# Sheet2.net
KiCad netlist of a schematic drawn in Altium Designer
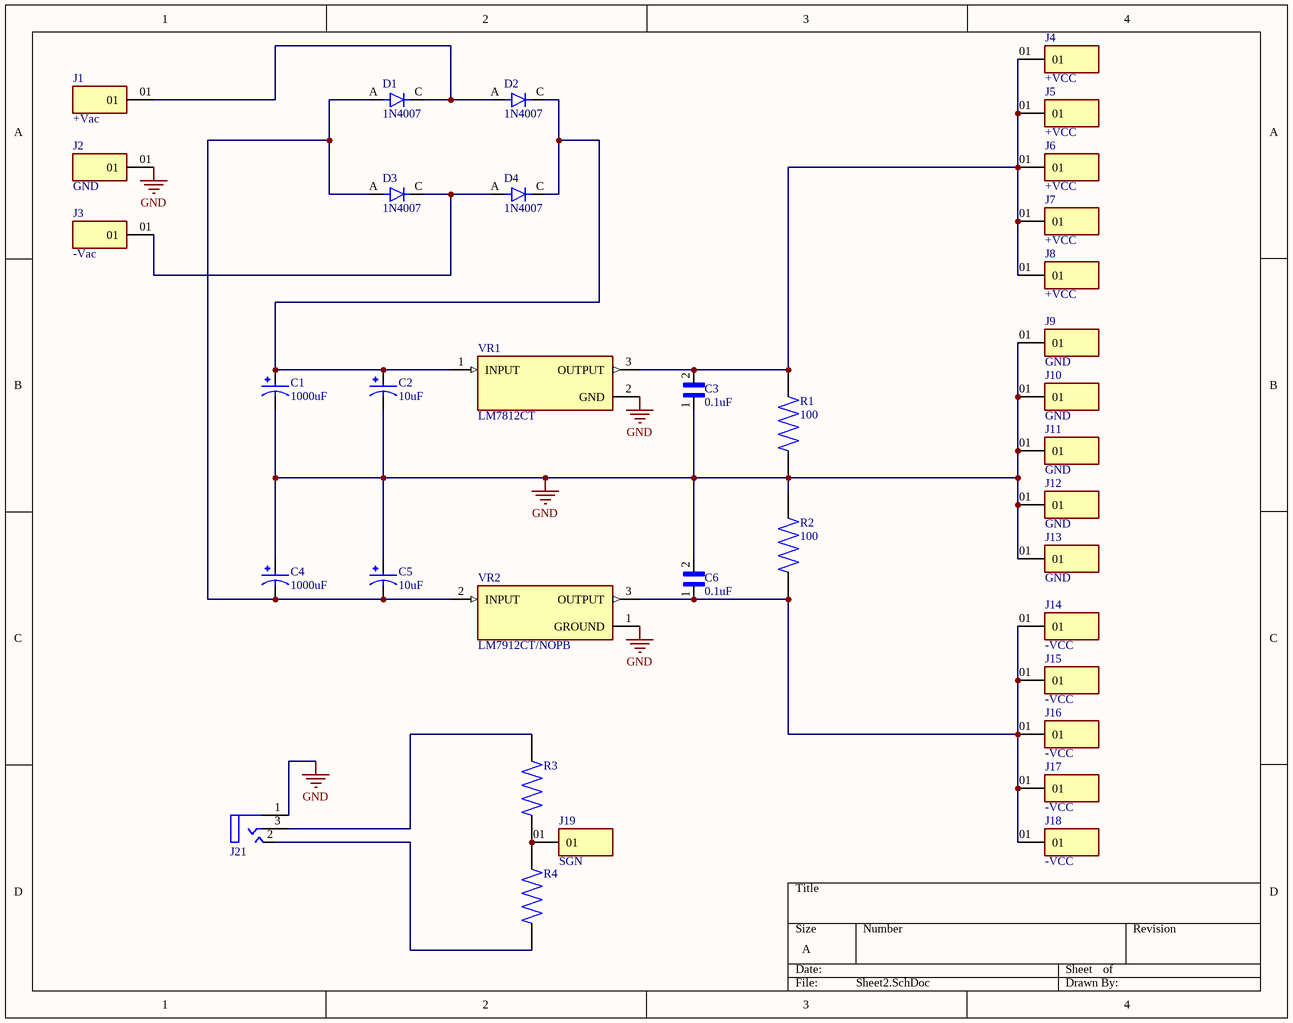
[diagram p0: Sheet2.SchDoc]

(export (version "E")
  (design (tool "Eeschema 10.0.6"))
  (components
    (comp (ref "C1")
      (value "1000uF")
      (footprint "CAPPRD750W80D1800H2500")
      (description "CAP ALUM 82UF 20% 350V RADIAL")
      (fields (field (name "MP") "EEU-EE2V820S") (field (name "MF") "Panasonic Electronic"))
      (libsource (lib "EEUEE2V820S") (part "EEUEE2V820S"))
    )
    (comp (ref "C2")
      (value "10uF")
      (footprint "CAPPRD750W80D1800H2500")
      (description "CAP ALUM 82UF 20% 350V RADIAL")
      (fields (field (name "MP") "EEU-EE2V820S") (field (name "MF") "Panasonic Electronic"))
      (libsource (lib "EEUEE2V820S") (part "EEUEE2V820S"))
    )
    (comp (ref "C3")
      (value "0.1uF")
      (footprint "CAPRB500W50L550T350H600:CAPRB500W50L550T350H600")
      (description "0.1ÂµF Â±10% 250V Ceramic Capacitor X7R Radial")
      (fields (field (name "MF") "TDK") (field (name "MP") "FG26X7R2E104KNT06"))
      (libsource (lib "FG26X7R2E104KNT06") (part "FG26X7R2E104KNT06"))
    )
    (comp (ref "C4")
      (value "1000uF")
      (footprint "CAPPRD750W80D1800H2500")
      (description "CAP ALUM 82UF 20% 350V RADIAL")
      (fields (field (name "MP") "EEU-EE2V820S") (field (name "MF") "Panasonic Electronic"))
      (libsource (lib "EEUEE2V820S") (part "EEUEE2V820S"))
    )
    (comp (ref "C5")
      (value "10uF")
      (footprint "CAPPRD750W80D1800H2500")
      (description "CAP ALUM 82UF 20% 350V RADIAL")
      (fields (field (name "MP") "EEU-EE2V820S") (field (name "MF") "Panasonic Electronic"))
      (libsource (lib "EEUEE2V820S") (part "EEUEE2V820S"))
    )
    (comp (ref "C6")
      (value "0.1uF")
      (footprint "CAPRB500W50L550T350H600:CAPRB500W50L550T350H600")
      (description "0.1ÂµF Â±10% 250V Ceramic Capacitor X7R Radial")
      (fields (field (name "MF") "TDK") (field (name "MP") "FG26X7R2E104KNT06"))
      (libsource (lib "FG26X7R2E104KNT06") (part "FG26X7R2E104KNT06"))
    )
    (comp (ref "D1")
      (value "1N4007")
      (footprint "DIOAD1060W80L520D270")
      (description "Diode Switching 1KV 1A 2-Pin DO-41")
      (libsource (lib "1N4007") (part "1N4007"))
    )
    (comp (ref "D2")
      (value "1N4007")
      (footprint "DIOAD1060W80L520D270")
      (description "Diode Switching 1KV 1A 2-Pin DO-41")
      (libsource (lib "1N4007") (part "1N4007"))
    )
    (comp (ref "D3")
      (value "1N4007")
      (footprint "DIOAD1060W80L520D270")
      (description "Diode Switching 1KV 1A 2-Pin DO-41")
      (libsource (lib "1N4007") (part "1N4007"))
    )
    (comp (ref "D4")
      (value "1N4007")
      (footprint "DIOAD1060W80L520D270")
      (description "Diode Switching 1KV 1A 2-Pin DO-41")
      (libsource (lib "1N4007") (part "1N4007"))
    )
    (comp (ref "J1")
      (value "+Vac")
      (footprint "SAMTEC_MTMM-101-XX-X-S-XXX:SAMTEC_MTMM-101-XX-X-S-XXX")
      (description "Connector Header position")
      (fields (field (name "MP") "MTMM-101-XX-X-S-XXX"))
      (libsource (lib "") (part "MTMM-101-XX-X-S-XXX_1"))
    )
    (comp (ref "J2")
      (value "GND")
      (footprint "SAMTEC_MTMM-101-XX-X-S-XXX:SAMTEC_MTMM-101-XX-X-S-XXX")
      (description "Connector Header position")
      (fields (field (name "MP") "MTMM-101-XX-X-S-XXX"))
      (libsource (lib "") (part "MTMM-101-XX-X-S-XXX_1"))
    )
    (comp (ref "J3")
      (value "-Vac")
      (footprint "SAMTEC_MTMM-101-XX-X-S-XXX:SAMTEC_MTMM-101-XX-X-S-XXX")
      (description "Connector Header position")
      (fields (field (name "MP") "MTMM-101-XX-X-S-XXX"))
      (libsource (lib "") (part "MTMM-101-XX-X-S-XXX_1"))
    )
    (comp (ref "J4")
      (value "+VCC")
      (footprint "SAMTEC_MTMM-101-XX-X-S-XXX:SAMTEC_MTMM-101-XX-X-S-XXX")
      (description "Connector Header position")
      (fields (field (name "MP") "MTMM-101-XX-X-S-XXX"))
      (libsource (lib "MTMM-101-XX-X-S-XXX") (part "MTMM-101-XX-X-S-XXX"))
    )
    (comp (ref "J5")
      (value "+VCC")
      (footprint "SAMTEC_MTMM-101-XX-X-S-XXX:SAMTEC_MTMM-101-XX-X-S-XXX")
      (description "Connector Header position")
      (fields (field (name "MP") "MTMM-101-XX-X-S-XXX"))
      (libsource (lib "MTMM-101-XX-X-S-XXX") (part "MTMM-101-XX-X-S-XXX"))
    )
    (comp (ref "J6")
      (value "+VCC")
      (footprint "SAMTEC_MTMM-101-XX-X-S-XXX:SAMTEC_MTMM-101-XX-X-S-XXX")
      (description "Connector Header position")
      (fields (field (name "MP") "MTMM-101-XX-X-S-XXX"))
      (libsource (lib "MTMM-101-XX-X-S-XXX") (part "MTMM-101-XX-X-S-XXX"))
    )
    (comp (ref "J7")
      (value "+VCC")
      (footprint "SAMTEC_MTMM-101-XX-X-S-XXX:SAMTEC_MTMM-101-XX-X-S-XXX")
      (description "Connector Header position")
      (fields (field (name "MP") "MTMM-101-XX-X-S-XXX"))
      (libsource (lib "MTMM-101-XX-X-S-XXX") (part "MTMM-101-XX-X-S-XXX"))
    )
    (comp (ref "J8")
      (value "+VCC")
      (footprint "SAMTEC_MTMM-101-XX-X-S-XXX:SAMTEC_MTMM-101-XX-X-S-XXX")
      (description "Connector Header position")
      (fields (field (name "MP") "MTMM-101-XX-X-S-XXX"))
      (libsource (lib "MTMM-101-XX-X-S-XXX") (part "MTMM-101-XX-X-S-XXX"))
    )
    (comp (ref "J9")
      (value "GND")
      (footprint "SAMTEC_MTMM-101-XX-X-S-XXX:SAMTEC_MTMM-101-XX-X-S-XXX")
      (description "Connector Header position")
      (fields (field (name "MP") "MTMM-101-XX-X-S-XXX"))
      (libsource (lib "MTMM-101-XX-X-S-XXX") (part "MTMM-101-XX-X-S-XXX"))
    )
    (comp (ref "J10")
      (value "GND")
      (footprint "SAMTEC_MTMM-101-XX-X-S-XXX:SAMTEC_MTMM-101-XX-X-S-XXX")
      (description "Connector Header position")
      (fields (field (name "MP") "MTMM-101-XX-X-S-XXX"))
      (libsource (lib "MTMM-101-XX-X-S-XXX") (part "MTMM-101-XX-X-S-XXX"))
    )
    (comp (ref "J11")
      (value "GND")
      (footprint "SAMTEC_MTMM-101-XX-X-S-XXX:SAMTEC_MTMM-101-XX-X-S-XXX")
      (description "Connector Header position")
      (fields (field (name "MP") "MTMM-101-XX-X-S-XXX"))
      (libsource (lib "MTMM-101-XX-X-S-XXX") (part "MTMM-101-XX-X-S-XXX"))
    )
    (comp (ref "J12")
      (value "GND")
      (footprint "SAMTEC_MTMM-101-XX-X-S-XXX:SAMTEC_MTMM-101-XX-X-S-XXX")
      (description "Connector Header position")
      (fields (field (name "MP") "MTMM-101-XX-X-S-XXX"))
      (libsource (lib "MTMM-101-XX-X-S-XXX") (part "MTMM-101-XX-X-S-XXX"))
    )
    (comp (ref "J13")
      (value "GND")
      (footprint "SAMTEC_MTMM-101-XX-X-S-XXX:SAMTEC_MTMM-101-XX-X-S-XXX")
      (description "Connector Header position")
      (fields (field (name "MP") "MTMM-101-XX-X-S-XXX"))
      (libsource (lib "MTMM-101-XX-X-S-XXX") (part "MTMM-101-XX-X-S-XXX"))
    )
    (comp (ref "J14")
      (value "-VCC")
      (footprint "SAMTEC_MTMM-101-XX-X-S-XXX:SAMTEC_MTMM-101-XX-X-S-XXX")
      (description "Connector Header position")
      (fields (field (name "MP") "MTMM-101-XX-X-S-XXX"))
      (libsource (lib "MTMM-101-XX-X-S-XXX") (part "MTMM-101-XX-X-S-XXX"))
    )
    (comp (ref "J15")
      (value "-VCC")
      (footprint "SAMTEC_MTMM-101-XX-X-S-XXX:SAMTEC_MTMM-101-XX-X-S-XXX")
      (description "Connector Header position")
      (fields (field (name "MP") "MTMM-101-XX-X-S-XXX"))
      (libsource (lib "MTMM-101-XX-X-S-XXX") (part "MTMM-101-XX-X-S-XXX"))
    )
    (comp (ref "J16")
      (value "-VCC")
      (footprint "SAMTEC_MTMM-101-XX-X-S-XXX:SAMTEC_MTMM-101-XX-X-S-XXX")
      (description "Connector Header position")
      (fields (field (name "MP") "MTMM-101-XX-X-S-XXX"))
      (libsource (lib "MTMM-101-XX-X-S-XXX") (part "MTMM-101-XX-X-S-XXX"))
    )
    (comp (ref "J17")
      (value "-VCC")
      (footprint "SAMTEC_MTMM-101-XX-X-S-XXX:SAMTEC_MTMM-101-XX-X-S-XXX")
      (description "Connector Header position")
      (fields (field (name "MP") "MTMM-101-XX-X-S-XXX"))
      (libsource (lib "MTMM-101-XX-X-S-XXX") (part "MTMM-101-XX-X-S-XXX"))
    )
    (comp (ref "J18")
      (value "-VCC")
      (footprint "SAMTEC_MTMM-101-XX-X-S-XXX:SAMTEC_MTMM-101-XX-X-S-XXX")
      (description "Connector Header position")
      (fields (field (name "MP") "MTMM-101-XX-X-S-XXX"))
      (libsource (lib "MTMM-101-XX-X-S-XXX") (part "MTMM-101-XX-X-S-XXX"))
    )
    (comp (ref "J19")
      (value "SGN")
      (footprint "SAMTEC_MTMM-101-XX-X-S-XXX:SAMTEC_MTMM-101-XX-X-S-XXX")
      (description "Connector Header position")
      (fields (field (name "MP") "MTMM-101-XX-X-S-XXX"))
      (libsource (lib "MTMM-101-XX-X-S-XXX") (part "MTMM-101-XX-X-S-XXX"))
    )
    (comp (ref "J21")
      (value "SJ1-3523N")
      (footprint "CUI_Devices_0_MFG")
      (libsource (lib "Conn_CUI_Devices_SJ1-3523N_eec") (part "SJ1-3523N"))
    )
    (comp (ref "R1")
      (value "100")
      (footprint "RESAD1100W55L680D260")
      (description "1.78 kOhms Â±1% 0.25W, 1/4W Through Hole Resistor Axial - Metal Film")
      (fields (field (name "MF") "Yageo") (field (name "MP") "MFR-25FBF52-1K"))
      (libsource (lib "MFR-25FBF52-1K") (part "MFR-25FBF52-1K"))
    )
    (comp (ref "R2")
      (value "100")
      (footprint "RESAD1100W55L680D260")
      (description "1.78 kOhms Â±1% 0.25W, 1/4W Through Hole Resistor Axial - Metal Film")
      (fields (field (name "MF") "Yageo") (field (name "MP") "MFR-25FBF52-1K"))
      (libsource (lib "MFR-25FBF52-1K") (part "MFR-25FBF52-1K"))
    )
    (comp (ref "R3")
      (value "MFR-25FBF52-1K")
      (footprint "RESAD1100W55L680D260")
      (description "1.78 kOhms Â±1% 0.25W, 1/4W Through Hole Resistor Axial - Metal Film")
      (fields (field (name "MF") "Yageo"))
      (libsource (lib "MFR-25FBF52-1K") (part "MFR-25FBF52-1K"))
    )
    (comp (ref "R4")
      (value "MFR-25FBF52-1K")
      (footprint "RESAD1100W55L680D260")
      (description "1.78 kOhms Â±1% 0.25W, 1/4W Through Hole Resistor Axial - Metal Film")
      (fields (field (name "MF") "Yageo"))
      (libsource (lib "MFR-25FBF52-1K") (part "MFR-25FBF52-1K"))
    )
    (comp (ref "VR1")
      (value "LM7812CT")
      (footprint "TO253P1057X470X2040-3")
      (description "Linear Voltage Regulator IC Positive Fixed 1 Output  1A TO-220-3")
      (fields (field (name "MF") "ON Semiconductor"))
      (libsource (lib "LM7812CT") (part "LM7812CT"))
    )
    (comp (ref "VR2")
      (value "LM7912CT/NOPB")
      (footprint "TO254P1054X470X1955-3")
      (description "1.5-A, negative linear voltage regulator")
      (fields (field (name "MF") "Texas Instruments"))
      (libsource (lib "LM7912CT_NOPB") (part "LM7912CT/NOPB"))
    )
  )
  (nets
    (net (code "1") (name "GND") (class "Default")
      (node (ref "C1") (pin "N") (pinfunction "N_N") (pintype "passive"))
      (node (ref "C2") (pin "N") (pinfunction "N_N") (pintype "passive"))
      (node (ref "C3") (pin "1") (pinfunction "1_1") (pintype "passive"))
      (node (ref "C4") (pin "P") (pinfunction "P_P") (pintype "passive"))
      (node (ref "C5") (pin "P") (pinfunction "P_P") (pintype "passive"))
      (node (ref "C6") (pin "2") (pinfunction "2_2") (pintype "passive"))
      (node (ref "J10") (pin "01") (pinfunction "01_01") (pintype "passive"))
      (node (ref "J11") (pin "01") (pinfunction "01_01") (pintype "passive"))
      (node (ref "J12") (pin "01") (pinfunction "01_01") (pintype "passive"))
      (node (ref "J13") (pin "01") (pinfunction "01_01") (pintype "passive"))
      (node (ref "J2") (pin "01") (pinfunction "01_01") (pintype "passive"))
      (node (ref "J21") (pin "1") (pinfunction "sleeve_1") (pintype "passive"))
      (node (ref "J9") (pin "01") (pinfunction "01_01") (pintype "passive"))
      (node (ref "R1") (pin "1") (pinfunction "1_1") (pintype "passive"))
      (node (ref "R2") (pin "2") (pinfunction "2_2") (pintype "passive"))
      (node (ref "VR1") (pin "2") (pinfunction "GND_2") (pintype "power_in"))
      (node (ref "VR2") (pin "1") (pinfunction "GROUND_1") (pintype "power_in"))
    )
    (net (code "2") (name "Net-(D1-PadC)") (class "Default")
      (node (ref "D1") (pin "C") (pinfunction "C_C") (pintype "passive"))
      (node (ref "D2") (pin "A") (pinfunction "A_A") (pintype "passive"))
      (node (ref "J1") (pin "01") (pinfunction "01_01") (pintype "passive"))
    )
    (net (code "3") (name "Net-(D3-PadC)") (class "Default")
      (node (ref "D3") (pin "C") (pinfunction "C_C") (pintype "passive"))
      (node (ref "D4") (pin "A") (pinfunction "A_A") (pintype "passive"))
      (node (ref "J3") (pin "01") (pinfunction "01_01") (pintype "passive"))
    )
    (net (code "4") (name "Net-(J19-Pad01)") (class "Default")
      (node (ref "J19") (pin "01") (pinfunction "01_01") (pintype "passive"))
      (node (ref "R3") (pin "1") (pinfunction "1_1") (pintype "passive"))
      (node (ref "R4") (pin "2") (pinfunction "2_2") (pintype "passive"))
    )
    (net (code "5") (name "Net-(J21-ring)") (class "Default")
      (node (ref "J21") (pin "3") (pinfunction "ring_3") (pintype "passive"))
      (node (ref "R3") (pin "2") (pinfunction "2_2") (pintype "passive"))
    )
    (net (code "6") (name "Net-(J21-tip)") (class "Default")
      (node (ref "J21") (pin "2") (pinfunction "tip_2") (pintype "passive"))
      (node (ref "R4") (pin "1") (pinfunction "1_1") (pintype "passive"))
    )
    (net (code "7") (name "Net-(VR1-INPUT)") (class "Default")
      (node (ref "C1") (pin "P") (pinfunction "P_P") (pintype "passive"))
      (node (ref "C2") (pin "P") (pinfunction "P_P") (pintype "passive"))
      (node (ref "D2") (pin "C") (pinfunction "C_C") (pintype "passive"))
      (node (ref "D4") (pin "C") (pinfunction "C_C") (pintype "passive"))
      (node (ref "VR1") (pin "1") (pinfunction "INPUT_1") (pintype "input"))
    )
    (net (code "8") (name "Net-(VR1-OUTPUT)") (class "Default")
      (node (ref "C3") (pin "2") (pinfunction "2_2") (pintype "passive"))
      (node (ref "J4") (pin "01") (pinfunction "01_01") (pintype "passive"))
      (node (ref "J5") (pin "01") (pinfunction "01_01") (pintype "passive"))
      (node (ref "J6") (pin "01") (pinfunction "01_01") (pintype "passive"))
      (node (ref "J7") (pin "01") (pinfunction "01_01") (pintype "passive"))
      (node (ref "J8") (pin "01") (pinfunction "01_01") (pintype "passive"))
      (node (ref "R1") (pin "2") (pinfunction "2_2") (pintype "passive"))
      (node (ref "VR1") (pin "3") (pinfunction "OUTPUT_3") (pintype "output"))
    )
    (net (code "9") (name "Net-(VR2-INPUT)") (class "Default")
      (node (ref "C4") (pin "N") (pinfunction "N_N") (pintype "passive"))
      (node (ref "C5") (pin "N") (pinfunction "N_N") (pintype "passive"))
      (node (ref "D1") (pin "A") (pinfunction "A_A") (pintype "passive"))
      (node (ref "D3") (pin "A") (pinfunction "A_A") (pintype "passive"))
      (node (ref "VR2") (pin "2") (pinfunction "INPUT_2") (pintype "input"))
    )
    (net (code "10") (name "Net-(VR2-OUTPUT)") (class "Default")
      (node (ref "C6") (pin "1") (pinfunction "1_1") (pintype "passive"))
      (node (ref "J14") (pin "01") (pinfunction "01_01") (pintype "passive"))
      (node (ref "J15") (pin "01") (pinfunction "01_01") (pintype "passive"))
      (node (ref "J16") (pin "01") (pinfunction "01_01") (pintype "passive"))
      (node (ref "J17") (pin "01") (pinfunction "01_01") (pintype "passive"))
      (node (ref "J18") (pin "01") (pinfunction "01_01") (pintype "passive"))
      (node (ref "R2") (pin "1") (pinfunction "1_1") (pintype "passive"))
      (node (ref "VR2") (pin "3") (pinfunction "OUTPUT_3") (pintype "output"))
    )
  )
)
